# telemetry-4L.net
KiCad netlist of a schematic drawn in EAGLE
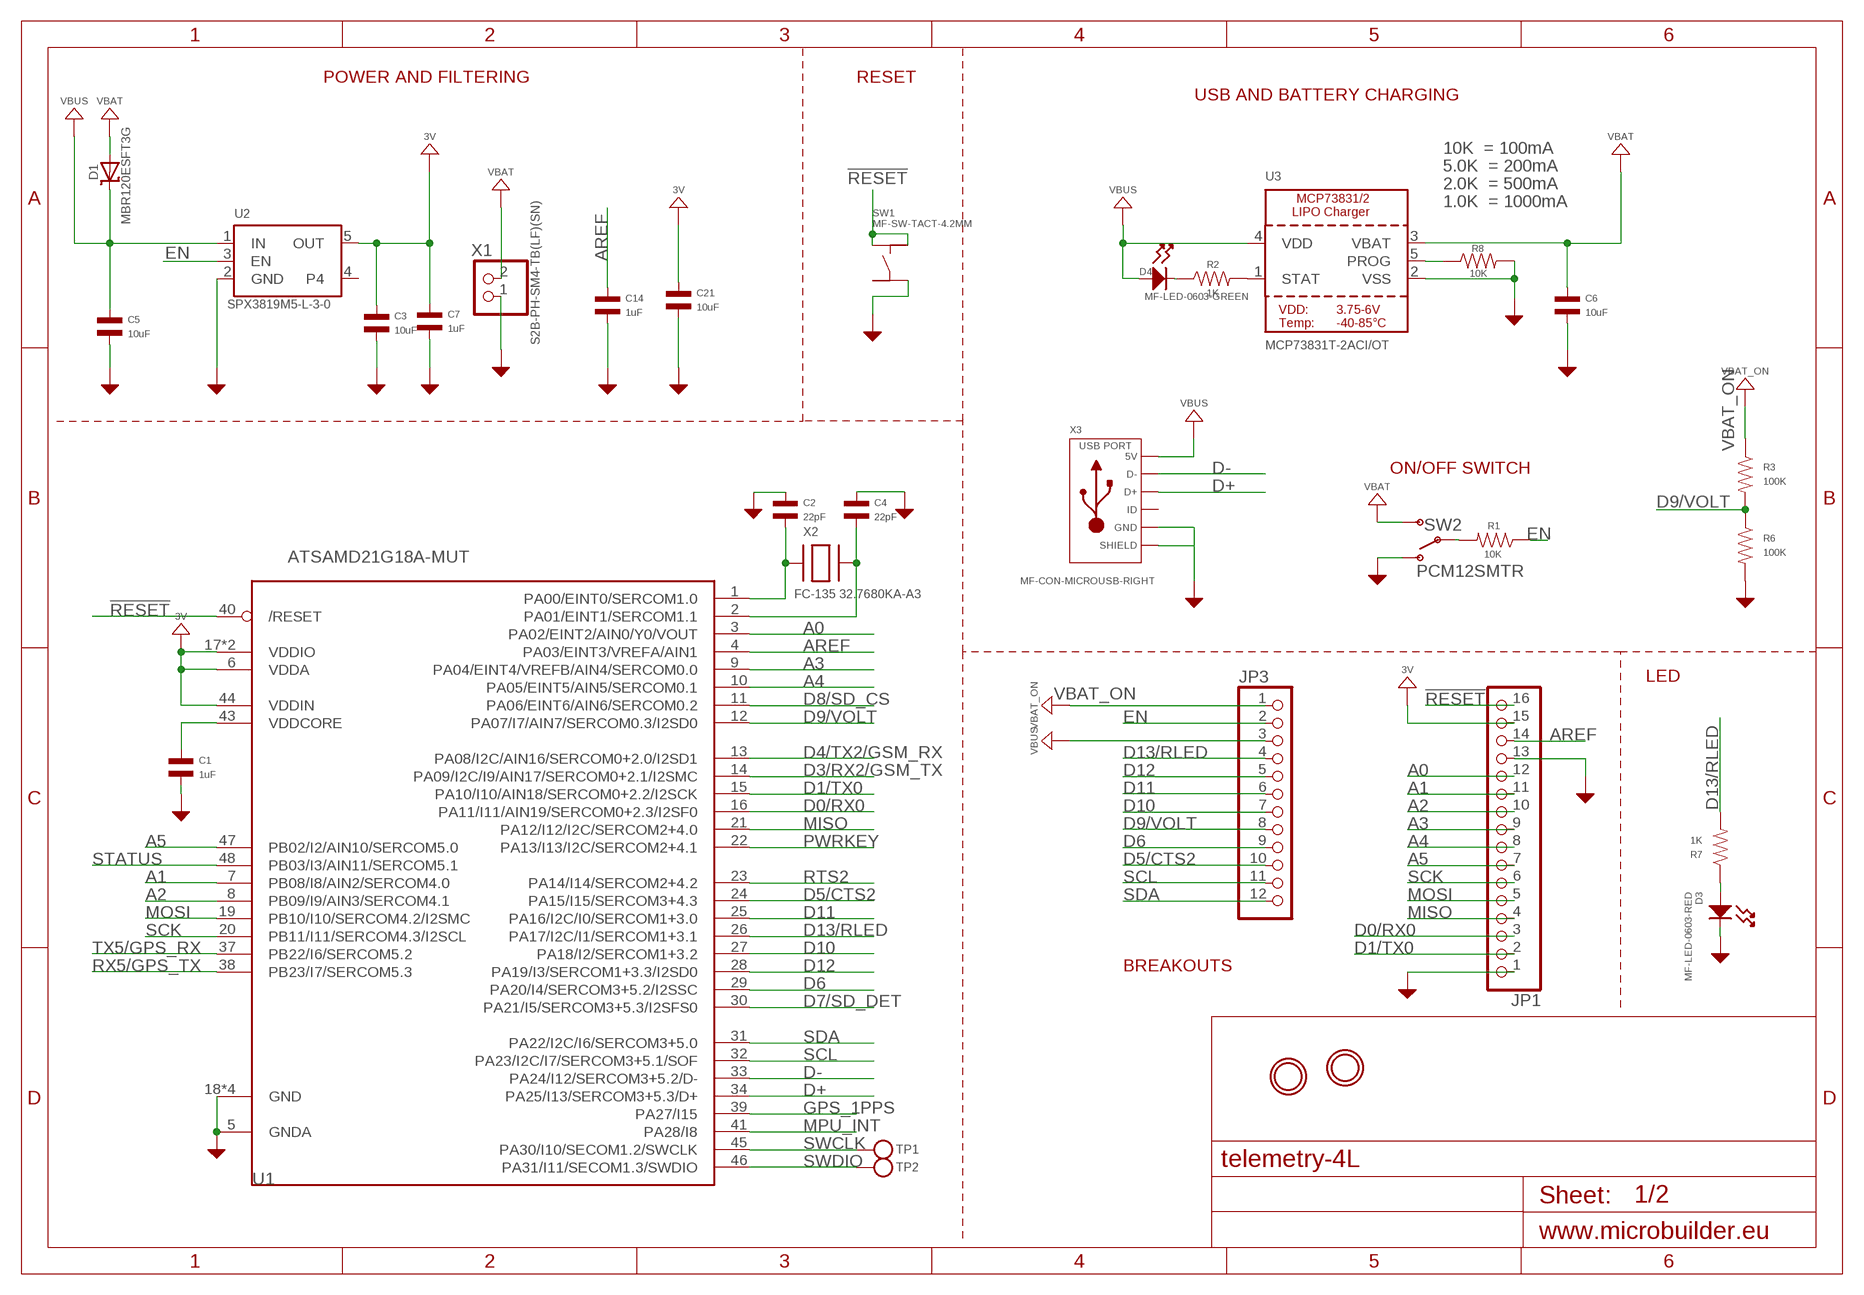
[diagram p0: schematic, sheet 1]
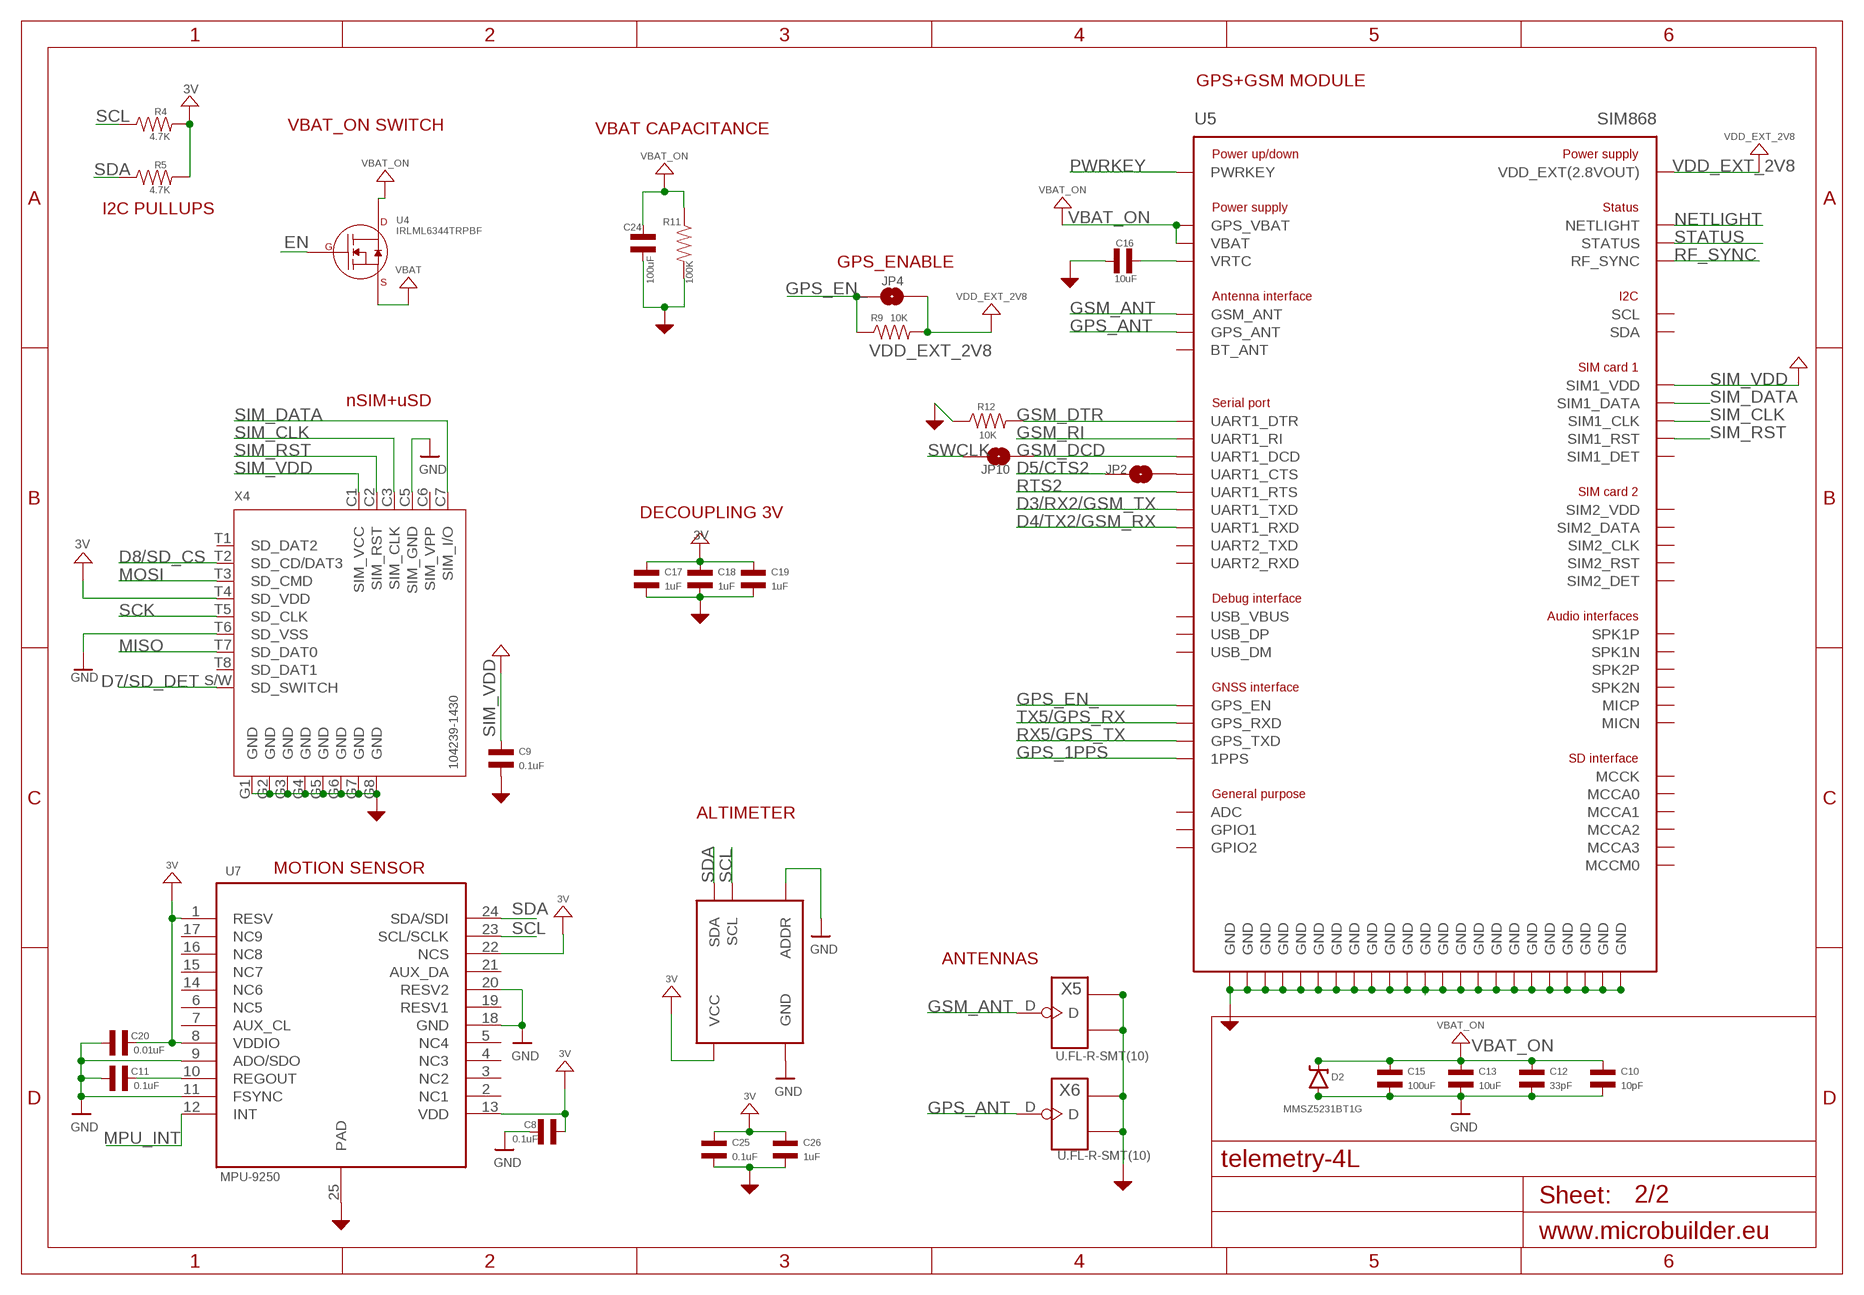
[diagram p1: schematic, sheet 2]

(export (version "E")
  (design (tool "Eeschema 10.0.6"))
  (components
    (comp (ref "C8")
      (value "0.1uF")
      (footprint "eagle-import:C0402")
      (libsource (lib "eagle-import") (part "CAPACITOR_NP_0402"))
    )
    (comp (ref "C9")
      (value "0.1uF")
      (footprint "eagle-import:C0402")
      (libsource (lib "eagle-import") (part "CAPACITOR_NP_0402"))
    )
    (comp (ref "C10")
      (value "10pF")
      (footprint "eagle-import:C0402")
      (fields (field (name "MPN") "GRM1555C1H100JA01J"))
      (libsource (lib "eagle-import") (part "CAPACITOR_NP_0402"))
    )
    (comp (ref "C11")
      (value "0.1uF")
      (footprint "eagle-import:C0402")
      (libsource (lib "eagle-import") (part "CAPACITOR_NP_0402"))
    )
    (comp (ref "C12")
      (value "33pF")
      (footprint "eagle-import:C0402")
      (fields (field (name "MPN") "GRM1555C1H330JA01D"))
      (libsource (lib "eagle-import") (part "CAPACITOR_NP_0402"))
    )
    (comp (ref "C13")
      (value "10uF")
      (footprint "eagle-import:C0603")
      (fields (field (name "MPN") "GRM188R60J106ME47D"))
      (libsource (lib "eagle-import") (part "CAPACITOR_NP_0603"))
    )
    (comp (ref "C15")
      (value "100uF")
      (footprint "eagle-import:C1206")
      (fields (field (name "MPN") "CL31A107MQHNNNE"))
      (libsource (lib "eagle-import") (part "CAPACITOR_NP_1206"))
    )
    (comp (ref "C16")
      (value "10uF")
      (footprint "eagle-import:C0603")
      (fields (field (name "MPN") "GRM188R60J106ME47D"))
      (libsource (lib "eagle-import") (part "CAPACITOR_NP_0603"))
    )
    (comp (ref "C17")
      (value "1uF")
      (footprint "eagle-import:C0402")
      (libsource (lib "eagle-import") (part "CAPACITOR_NP_0402"))
    )
    (comp (ref "C18")
      (value "1uF")
      (footprint "eagle-import:C0402")
      (libsource (lib "eagle-import") (part "CAPACITOR_NP_0402"))
    )
    (comp (ref "C19")
      (value "1uF")
      (footprint "eagle-import:C0402")
      (libsource (lib "eagle-import") (part "CAPACITOR_NP_0402"))
    )
    (comp (ref "C20")
      (value "0.01uF")
      (footprint "eagle-import:C0402")
      (libsource (lib "eagle-import") (part "CAPACITOR_NP_0402"))
    )
    (comp (ref "C24")
      (value "100uF")
      (footprint "eagle-import:C1206")
      (fields (field (name "MPN") "CL31A107MQHNNNE"))
      (libsource (lib "eagle-import") (part "CAPACITOR_NP_1206"))
    )
    (comp (ref "C25")
      (value "0.1uF")
      (footprint "eagle-import:C0402")
      (libsource (lib "eagle-import") (part "CAPACITOR_NP_0402"))
    )
    (comp (ref "C26")
      (value "1uF")
      (footprint "eagle-import:C0402")
      (libsource (lib "eagle-import") (part "CAPACITOR_NP_0402"))
    )
    (comp (ref "D2")
      (value "MMSZ5231BT1G")
      (footprint "eagle-import:SOD-123")
      (fields (field (name "MFR") "ON SEMICONDUCTOR"))
      (libsource (lib "eagle-import") (part "MMSZ5231BT1G"))
    )
    (comp (ref "JP2")
      (value "JUMPER-PAD-2-NOYES_SILK")
      (footprint "eagle-import:PAD-JUMPER-2-NO_YES_SILK")
      (libsource (lib "eagle-import") (part "JUMPER-PAD-2-NOYES_SILK"))
    )
    (comp (ref "JP4")
      (value "JUMPER-PAD-2-NOYES_SILK")
      (footprint "eagle-import:PAD-JUMPER-2-NO_YES_SILK")
      (libsource (lib "eagle-import") (part "JUMPER-PAD-2-NOYES_SILK"))
    )
    (comp (ref "JP10")
      (value "JUMPER-PAD-2-NOYES_SILK")
      (footprint "eagle-import:PAD-JUMPER-2-NO_YES_SILK")
      (libsource (lib "eagle-import") (part "JUMPER-PAD-2-NOYES_SILK"))
    )
    (comp (ref "R4")
      (value "4.7K")
      (footprint "eagle-import:R0402")
      (libsource (lib "eagle-import") (part "RESISTOR_0402"))
    )
    (comp (ref "R5")
      (value "4.7K")
      (footprint "eagle-import:R0402")
      (libsource (lib "eagle-import") (part "RESISTOR_0402"))
    )
    (comp (ref "R9")
      (value "10K")
      (footprint "eagle-import:R0402")
      (libsource (lib "eagle-import") (part "RESISTOR_0402"))
    )
    (comp (ref "R11")
      (value "100K")
      (footprint "eagle-import:R0402")
      (libsource (lib "eagle-import") (part "RESISTOR_0402"))
    )
    (comp (ref "R12")
      (value "10K")
      (footprint "eagle-import:R0402")
      (libsource (lib "eagle-import") (part "RESISTOR_0402"))
    )
    (comp (ref "U4")
      (value "IRLML6344TRPBF")
      (footprint "eagle-import:SOT-23-3")
      (fields (field (name "HOUSEPART") "NO"))
      (libsource (lib "eagle-import") (part "N-CHANNEL_FET_SOT-23-3"))
    )
    (comp (ref "U5")
      (value "SIM868")
      (footprint "eagle-import:SIM868")
      (libsource (lib "eagle-import") (part "SIM868"))
    )
    (comp (ref "U6")
      (value "BMP280")
      (footprint "eagle-import:LGA-8")
      (libsource (lib "eagle-import") (part "BMP280"))
    )
    (comp (ref "U7")
      (value "MPU-9250")
      (footprint "eagle-import:LEAD-QFN24")
      (libsource (lib "eagle-import") (part "MPU-9250"))
    )
    (comp (ref "X4")
      (value "104239-1430")
      (footprint "eagle-import:MOLEX-SD+SIM-104239")
      (fields (field (name "MPN") "VSHO-21-3301") (field (name "MPN_1") "104239-1430"))
      (libsource (lib "eagle-import") (part "MOLEX-SD+SIM-104239"))
    )
    (comp (ref "X5")
      (value "U.FL-R-SMT(10)")
      (footprint "eagle-import:U-FL3P-SMD-2.6X2.6X1.0MM")
      (libsource (lib "eagle-import") (part "ANTENNA-CONN-U-FL(3P)"))
    )
    (comp (ref "X6")
      (value "U.FL-R-SMT(10)")
      (footprint "eagle-import:U-FL3P-SMD-2.6X2.6X1.0MM")
      (libsource (lib "eagle-import") (part "ANTENNA-CONN-U-FL(3P)"))
    )
    (comp (ref "C1")
      (value "1uF")
      (footprint "eagle-import:C0402")
      (libsource (lib "eagle-import") (part "CAPACITOR_NP_0402"))
    )
    (comp (ref "C2")
      (value "22pF")
      (footprint "eagle-import:C0402")
      (libsource (lib "eagle-import") (part "CAPACITOR_NP_0402"))
    )
    (comp (ref "C3")
      (value "10uF")
      (footprint "eagle-import:C0603")
      (fields (field (name "MPN") "GRM188R60J106ME47D"))
      (libsource (lib "eagle-import") (part "CAPACITOR_NP_0603"))
    )
    (comp (ref "C4")
      (value "22pF")
      (footprint "eagle-import:C0402")
      (libsource (lib "eagle-import") (part "CAPACITOR_NP_0402"))
    )
    (comp (ref "C5")
      (value "10uF")
      (footprint "eagle-import:C0603")
      (fields (field (name "MPN") "GRM188R60J106ME47D"))
      (libsource (lib "eagle-import") (part "CAPACITOR_NP_0603"))
    )
    (comp (ref "C6")
      (value "10uF")
      (footprint "eagle-import:C0603")
      (fields (field (name "MPN") "GRM188R60J106ME47D"))
      (libsource (lib "eagle-import") (part "CAPACITOR_NP_0603"))
    )
    (comp (ref "C7")
      (value "1uF")
      (footprint "eagle-import:C0402")
      (libsource (lib "eagle-import") (part "CAPACITOR_NP_0402"))
    )
    (comp (ref "C14")
      (value "1uF")
      (footprint "eagle-import:C0402")
      (libsource (lib "eagle-import") (part "CAPACITOR_NP_0402"))
    )
    (comp (ref "C21")
      (value "10uF")
      (footprint "eagle-import:C0603")
      (fields (field (name "MPN") "GRM188R60J106ME47D"))
      (libsource (lib "eagle-import") (part "CAPACITOR_NP_0603"))
    )
    (comp (ref "D1")
      (value "MBR120ESFT3G")
      (footprint "eagle-import:SOD-123")
      (libsource (lib "eagle-import") (part "DIODE-SCHOTTKYSOD-123"))
    )
    (comp (ref "D3")
      (value "MF-LED-0603-RED")
      (footprint "eagle-import:LED0603")
      (fields (field (name "HOUSEPART") "YES"))
      (libsource (lib "eagle-import") (part "LED_SINGLE-0603-RED"))
    )
    (comp (ref "D4")
      (value "MF-LED-0603-GREEN")
      (footprint "eagle-import:LED0603")
      (fields (field (name "HOUSEPART") "YES"))
      (libsource (lib "eagle-import") (part "LED_SINGLE-0603-GREEN"))
    )
    (comp (ref "JP1")
      (value "HEADER-1X16ROUND")
      (footprint "eagle-import:1X16_ROUND")
      (libsource (lib "eagle-import") (part "HEADER-1X16ROUND"))
    )
    (comp (ref "JP3")
      (value "HEADER-1X12")
      (footprint "eagle-import:1X12_ROUND")
      (libsource (lib "eagle-import") (part "HEADER-1X12"))
    )
    (comp (ref "R1")
      (value "10K")
      (footprint "eagle-import:R0402")
      (libsource (lib "eagle-import") (part "RESISTOR_0402"))
    )
    (comp (ref "R2")
      (value "1K")
      (footprint "eagle-import:R0402")
      (libsource (lib "eagle-import") (part "RESISTOR_0402"))
    )
    (comp (ref "R3")
      (value "100K")
      (footprint "eagle-import:R0402")
      (libsource (lib "eagle-import") (part "RESISTOR_0402"))
    )
    (comp (ref "R6")
      (value "100K")
      (footprint "eagle-import:R0402")
      (libsource (lib "eagle-import") (part "RESISTOR_0402"))
    )
    (comp (ref "R7")
      (value "1K")
      (footprint "eagle-import:R0402")
      (libsource (lib "eagle-import") (part "RESISTOR_0402"))
    )
    (comp (ref "R8")
      (value "10K")
      (footprint "eagle-import:R0402")
      (libsource (lib "eagle-import") (part "RESISTOR_0402"))
    )
    (comp (ref "SW1")
      (value "MF-SW-TACT-4.2MM")
      (footprint "eagle-import:TACT4.2MM")
      (fields (field (name "HOUSEPART") "YES"))
      (libsource (lib "eagle-import") (part "TACT_4.2MM"))
    )
    (comp (ref "SW2")
      (value "PCM12SMTR")
      (footprint "eagle-import:KPS-1290")
      (libsource (lib "eagle-import") (part "SWITCH_SPDT"))
    )
    (comp (ref "TP1")
      (value "TESTPOINTROUND1.5MM")
      (footprint "eagle-import:TESTPOINT_ROUND_1.5MM")
      (libsource (lib "eagle-import") (part "TESTPOINTROUND1.5MM"))
    )
    (comp (ref "TP2")
      (value "TESTPOINTROUND1.5MM")
      (footprint "eagle-import:TESTPOINT_ROUND_1.5MM")
      (libsource (lib "eagle-import") (part "TESTPOINTROUND1.5MM"))
    )
    (comp (ref "U$31")
      (value "MOUNTINGHOLE2.5")
      (footprint "eagle-import:MOUNTINGHOLE_2.5_PLATED")
      (libsource (lib "eagle-import") (part "MOUNTINGHOLE2.5"))
    )
    (comp (ref "U$32")
      (value "MOUNTINGHOLE2.5")
      (footprint "eagle-import:MOUNTINGHOLE_2.5_PLATED")
      (libsource (lib "eagle-import") (part "MOUNTINGHOLE2.5"))
    )
    (comp (ref "U1")
      (value "ATSAMD21G18A-MUT")
      (footprint "eagle-import:TQFN48_7MM")
      (libsource (lib "eagle-import") (part "ATSAMD21J_QFN"))
    )
    (comp (ref "U2")
      (value "SPX3819M5-L-3-0")
      (footprint "eagle-import:SOT23-5")
      (libsource (lib "eagle-import") (part "VREG_SOT23-5"))
    )
    (comp (ref "U3")
      (value "MCP73831T-2ACI/OT")
      (footprint "eagle-import:SOT23-5")
      (libsource (lib "eagle-import") (part "MCP73831/2"))
    )
    (comp (ref "X1")
      (value "S2B-PH-SM4-TB(LF)(SN)")
      (footprint "eagle-import:JSTPH2")
      (libsource (lib "eagle-import") (part "CON_JST_PH_2PIN"))
    )
    (comp (ref "X2")
      (value "FC-135 32.7680KA-A3")
      (footprint "eagle-import:XTAL3215")
      (libsource (lib "eagle-import") (part "XTAL-3.2X1.5"))
    )
    (comp (ref "X3")
      (value "MF-CON-MICROUSB-RIGHT")
      (footprint "eagle-import:MICROUSB-RIGHT")
      (fields (field (name "HOUSEPART") "YES"))
      (libsource (lib "eagle-import") (part "USB_MICRO_RIGHT"))
    )
  )
  (nets
    (net (code "1") (name "+3V") (class "Default")
      (node (ref "C17") (pin "P$1") (pinfunction "P$1_P$1") (pintype "passive"))
      (node (ref "C18") (pin "P$1") (pinfunction "P$1_P$1") (pintype "passive"))
      (node (ref "C19") (pin "P$1") (pinfunction "P$1_P$1") (pintype "passive"))
      (node (ref "C20") (pin "P$2") (pinfunction "P$2_P$2") (pintype "passive"))
      (node (ref "C21") (pin "P$1") (pinfunction "P$1_P$1") (pintype "passive"))
      (node (ref "C25") (pin "P$1") (pinfunction "P$1_P$1") (pintype "passive"))
      (node (ref "C26") (pin "P$1") (pinfunction "P$1_P$1") (pintype "passive"))
      (node (ref "C3") (pin "P$1") (pinfunction "P$1_P$1") (pintype "passive"))
      (node (ref "C7") (pin "P$1") (pinfunction "P$1_P$1") (pintype "passive"))
      (node (ref "C8") (pin "P$2") (pinfunction "P$2_P$2") (pintype "passive"))
      (node (ref "JP1") (pin "15") (pinfunction "15_15") (pintype "passive"))
      (node (ref "R4") (pin "P$2") (pinfunction "P$2_P$2") (pintype "passive"))
      (node (ref "R5") (pin "P$2") (pinfunction "P$2_P$2") (pintype "passive"))
      (node (ref "U1") (pin "17") (pinfunction "VDDIO_17") (pintype "power_in"))
      (node (ref "U1") (pin "36") (pinfunction "VDDIO_36") (pintype "power_in"))
      (node (ref "U1") (pin "44") (pinfunction "VDDIN_44") (pintype "power_in"))
      (node (ref "U1") (pin "6") (pinfunction "VDDA_6") (pintype "power_in"))
      (node (ref "U2") (pin "5") (pinfunction "OUT_5") (pintype "power_in"))
      (node (ref "U6") (pin "P2") (pinfunction "VCC_P2") (pintype "bidirectional"))
      (node (ref "U6") (pin "P6") (pinfunction "VCC_P6") (pintype "bidirectional"))
      (node (ref "U6") (pin "P8") (pinfunction "VCC_P8") (pintype "bidirectional"))
      (node (ref "U7") (pin "1") (pinfunction "RESV_1") (pintype "bidirectional"))
      (node (ref "U7") (pin "13") (pinfunction "VDD_13") (pintype "bidirectional"))
      (node (ref "U7") (pin "22") (pinfunction "NCS_22") (pintype "bidirectional"))
      (node (ref "U7") (pin "8") (pinfunction "VDDIO_8") (pintype "bidirectional"))
      (node (ref "X4") (pin "T4") (pinfunction "SD_VDD_T4") (pintype "bidirectional"))
    )
    (net (code "2") (name "A0") (class "Default")
      (node (ref "JP1") (pin "12") (pinfunction "12_12") (pintype "passive"))
      (node (ref "U1") (pin "3") (pinfunction "PA02/EINT2/AIN0/Y0/VOUT_3") (pintype "bidirectional"))
    )
    (net (code "3") (name "A1") (class "Default")
      (node (ref "JP1") (pin "11") (pinfunction "11_11") (pintype "passive"))
      (node (ref "U1") (pin "7") (pinfunction "PB08/I8/AIN2/SERCOM4.0_7") (pintype "bidirectional"))
    )
    (net (code "4") (name "A2") (class "Default")
      (node (ref "JP1") (pin "10") (pinfunction "10_10") (pintype "passive"))
      (node (ref "U1") (pin "8") (pinfunction "PB09/I9/AIN3/SERCOM4.1_8") (pintype "bidirectional"))
    )
    (net (code "5") (name "A3") (class "Default")
      (node (ref "JP1") (pin "9") (pinfunction "9_9") (pintype "passive"))
      (node (ref "U1") (pin "9") (pinfunction "PA04/EINT4/VREFB/AIN4/SERCOM0.0_9") (pintype "bidirectional"))
    )
    (net (code "6") (name "A4") (class "Default")
      (node (ref "JP1") (pin "8") (pinfunction "8_8") (pintype "passive"))
      (node (ref "U1") (pin "10") (pinfunction "PA05/EINT5/AIN5/SERCOM0.1_10") (pintype "bidirectional"))
    )
    (net (code "7") (name "A5") (class "Default")
      (node (ref "JP1") (pin "7") (pinfunction "7_7") (pintype "passive"))
      (node (ref "U1") (pin "47") (pinfunction "PB02/I2/AIN10/SERCOM5.0_47") (pintype "bidirectional"))
    )
    (net (code "8") (name "AREF") (class "Default")
      (node (ref "C14") (pin "P$1") (pinfunction "P$1_P$1") (pintype "passive"))
      (node (ref "JP1") (pin "14") (pinfunction "14_14") (pintype "passive"))
      (node (ref "U1") (pin "4") (pinfunction "PA03/EINT3/VREFA/AIN1_4") (pintype "bidirectional"))
    )
    (net (code "9") (name "D+") (class "Default")
      (node (ref "U1") (pin "34") (pinfunction "PA25/I13/SERCOM3+5.3/D+_34") (pintype "bidirectional"))
      (node (ref "X3") (pin "3") (pinfunction "D+_3") (pintype "bidirectional"))
    )
    (net (code "10") (name "D-") (class "Default")
      (node (ref "U1") (pin "33") (pinfunction "PA24/I12/SERCOM3+5.2/D-_33") (pintype "bidirectional"))
      (node (ref "X3") (pin "2") (pinfunction "D-_2") (pintype "bidirectional"))
    )
    (net (code "11") (name "D0{slash}RX0") (class "Default")
      (node (ref "JP1") (pin "3") (pinfunction "3_3") (pintype "passive"))
      (node (ref "U1") (pin "16") (pinfunction "PA11/I11/AIN19/SERCOM0+2.3/I2SF0_16") (pintype "bidirectional"))
    )
    (net (code "12") (name "D1{slash}TX0") (class "Default")
      (node (ref "JP1") (pin "2") (pinfunction "2_2") (pintype "passive"))
      (node (ref "U1") (pin "15") (pinfunction "PA10/I10/AIN18/SERCOM0+2.2/I2SCK_15") (pintype "bidirectional"))
    )
    (net (code "13") (name "D3{slash}RX2{slash}GSM_TX") (class "Default")
      (node (ref "U1") (pin "14") (pinfunction "PA09/I2C/I9/AIN17/SERCOM0+2.1/I2SMC_14") (pintype "bidirectional"))
      (node (ref "U5") (pin "1_") (pinfunction "UART1_TXD_1_") (pintype "output"))
    )
    (net (code "14") (name "D4{slash}TX2{slash}GSM_RX") (class "Default")
      (node (ref "U1") (pin "13") (pinfunction "PA08/I2C/AIN16/SERCOM0+2.0/I2SD1_13") (pintype "bidirectional"))
      (node (ref "U5") (pin "2_") (pinfunction "UART1_RXD_2_") (pintype "input"))
    )
    (net (code "15") (name "D5{slash}CTS2") (class "Default")
      (node (ref "JP2") (pin "1") (pinfunction "1_1") (pintype "passive"))
      (node (ref "JP3") (pin "10") (pinfunction "10_10") (pintype "passive"))
      (node (ref "U1") (pin "24") (pinfunction "PA15/I15/SERCOM3+4.3_24") (pintype "bidirectional"))
    )
    (net (code "16") (name "D6") (class "Default")
      (node (ref "JP3") (pin "9") (pinfunction "9_9") (pintype "passive"))
      (node (ref "U1") (pin "29") (pinfunction "PA20/I4/SERCOM3+5.2/I2SSC_29") (pintype "bidirectional"))
    )
    (net (code "17") (name "D7{slash}SD_DET") (class "Default")
      (node (ref "U1") (pin "30") (pinfunction "PA21/I5/SERCOM3+5.3/I2SFS0_30") (pintype "bidirectional"))
      (node (ref "X4") (pin "S/W") (pinfunction "SD_SWITCH_S/W") (pintype "bidirectional"))
    )
    (net (code "18") (name "D8{slash}SD_CS") (class "Default")
      (node (ref "U1") (pin "11") (pinfunction "PA06/EINT6/AIN6/SERCOM0.2_11") (pintype "bidirectional"))
      (node (ref "X4") (pin "T2") (pinfunction "SD_CD/DAT3_T2") (pintype "bidirectional"))
    )
    (net (code "19") (name "D9{slash}VOLT") (class "Default")
      (node (ref "JP3") (pin "8") (pinfunction "8_8") (pintype "passive"))
      (node (ref "R3") (pin "P$2") (pinfunction "P$2_P$2") (pintype "passive"))
      (node (ref "R6") (pin "P$1") (pinfunction "P$1_P$1") (pintype "passive"))
      (node (ref "U1") (pin "12") (pinfunction "PA07/I7/AIN7/SERCOM0.3/I2SD0_12") (pintype "bidirectional"))
    )
    (net (code "20") (name "D10") (class "Default")
      (node (ref "JP3") (pin "7") (pinfunction "7_7") (pintype "passive"))
      (node (ref "U1") (pin "27") (pinfunction "PA18/I2/SERCOM1+3.2_27") (pintype "bidirectional"))
    )
    (net (code "21") (name "D11") (class "Default")
      (node (ref "JP3") (pin "6") (pinfunction "6_6") (pintype "passive"))
      (node (ref "U1") (pin "25") (pinfunction "PA16/I2C/I0/SERCOM1+3.0_25") (pintype "bidirectional"))
    )
    (net (code "22") (name "D12") (class "Default")
      (node (ref "JP3") (pin "5") (pinfunction "5_5") (pintype "passive"))
      (node (ref "U1") (pin "28") (pinfunction "PA19/I3/SERCOM1+3.3/I2SD0_28") (pintype "bidirectional"))
    )
    (net (code "23") (name "D13{slash}RLED") (class "Default")
      (node (ref "JP3") (pin "4") (pinfunction "4_4") (pintype "passive"))
      (node (ref "R7") (pin "P$2") (pinfunction "P$2_P$2") (pintype "passive"))
      (node (ref "U1") (pin "26") (pinfunction "PA17/I2C/I1/SERCOM1+3.1_26") (pintype "bidirectional"))
    )
    (net (code "24") (name "EN") (class "Default")
      (node (ref "JP3") (pin "2") (pinfunction "2_2") (pintype "passive"))
      (node (ref "R1") (pin "P$1") (pinfunction "P$1_P$1") (pintype "passive"))
      (node (ref "U2") (pin "3") (pinfunction "EN_3") (pintype "input"))
      (node (ref "U4") (pin "P$1") (pinfunction "GATE_P$1") (pintype "bidirectional"))
    )
    (net (code "25") (name "GND") (class "Default")
      (node (ref "C1") (pin "P$2") (pinfunction "P$2_P$2") (pintype "passive"))
      (node (ref "C10") (pin "P$2") (pinfunction "P$2_P$2") (pintype "passive"))
      (node (ref "C11") (pin "P$1") (pinfunction "P$1_P$1") (pintype "passive"))
      (node (ref "C12") (pin "P$2") (pinfunction "P$2_P$2") (pintype "passive"))
      (node (ref "C13") (pin "P$2") (pinfunction "P$2_P$2") (pintype "passive"))
      (node (ref "C14") (pin "P$2") (pinfunction "P$2_P$2") (pintype "passive"))
      (node (ref "C15") (pin "P$2") (pinfunction "P$2_P$2") (pintype "passive"))
      (node (ref "C16") (pin "P$1") (pinfunction "P$1_P$1") (pintype "passive"))
      (node (ref "C17") (pin "P$2") (pinfunction "P$2_P$2") (pintype "passive"))
      (node (ref "C18") (pin "P$2") (pinfunction "P$2_P$2") (pintype "passive"))
      (node (ref "C19") (pin "P$2") (pinfunction "P$2_P$2") (pintype "passive"))
      (node (ref "C2") (pin "P$1") (pinfunction "P$1_P$1") (pintype "passive"))
      (node (ref "C20") (pin "P$1") (pinfunction "P$1_P$1") (pintype "passive"))
      (node (ref "C21") (pin "P$2") (pinfunction "P$2_P$2") (pintype "passive"))
      (node (ref "C24") (pin "P$2") (pinfunction "P$2_P$2") (pintype "passive"))
      (node (ref "C25") (pin "P$2") (pinfunction "P$2_P$2") (pintype "passive"))
      (node (ref "C26") (pin "P$2") (pinfunction "P$2_P$2") (pintype "passive"))
      (node (ref "C3") (pin "P$2") (pinfunction "P$2_P$2") (pintype "passive"))
      (node (ref "C4") (pin "P$1") (pinfunction "P$1_P$1") (pintype "passive"))
      (node (ref "C5") (pin "P$2") (pinfunction "P$2_P$2") (pintype "passive"))
      (node (ref "C6") (pin "P$2") (pinfunction "P$2_P$2") (pintype "passive"))
      (node (ref "C7") (pin "P$2") (pinfunction "P$2_P$2") (pintype "passive"))
      (node (ref "C8") (pin "P$1") (pinfunction "P$1_P$1") (pintype "passive"))
      (node (ref "C9") (pin "P$2") (pinfunction "P$2_P$2") (pintype "passive"))
      (node (ref "D2") (pin "A") (pinfunction "A_A") (pintype "passive"))
      (node (ref "D3") (pin "CATHODE") (pinfunction "CATHODE_CATHODE") (pintype "power_in"))
      (node (ref "JP1") (pin "1") (pinfunction "1_1") (pintype "passive"))
      (node (ref "JP1") (pin "13") (pinfunction "13_13") (pintype "passive"))
      (node (ref "R11") (pin "P$2") (pinfunction "P$2_P$2") (pintype "passive"))
      (node (ref "R12") (pin "P$1") (pinfunction "P$1_P$1") (pintype "passive"))
      (node (ref "R6") (pin "P$2") (pinfunction "P$2_P$2") (pintype "passive"))
      (node (ref "R8") (pin "P$2") (pinfunction "P$2_P$2") (pintype "passive"))
      (node (ref "SW1") (pin "P$4") (pinfunction "P$4_P$4") (pintype "bidirectional"))
      (node (ref "SW2") (pin "O") (pinfunction "O_O") (pintype "passive"))
      (node (ref "U1") (pin "18") (pinfunction "GND_18") (pintype "power_in"))
      (node (ref "U1") (pin "35") (pinfunction "GND_35") (pintype "power_in"))
      (node (ref "U1") (pin "42") (pinfunction "GND_42") (pintype "power_in"))
      (node (ref "U1") (pin "5") (pinfunction "GNDA_5") (pintype "power_in"))
      (node (ref "U1") (pin "THERMAL") (pinfunction "GND_THERMAL") (pintype "power_in"))
      (node (ref "U2") (pin "2") (pinfunction "GND_2") (pintype "power_in"))
      (node (ref "U3") (pin "2") (pinfunction "VSS_2") (pintype "power_in"))
      (node (ref "U5") (pin "13_") (pinfunction "GND_13_") (pintype "power_in"))
      (node (ref "U5") (pin "19_") (pinfunction "GND_19_") (pintype "power_in"))
      (node (ref "U5") (pin "21_") (pinfunction "GND_21_") (pintype "power_in"))
      (node (ref "U5") (pin "27_") (pinfunction "GND_27_") (pintype "power_in"))
      (node (ref "U5") (pin "30_") (pinfunction "GND_30_") (pintype "power_in"))
      (node (ref "U5") (pin "31_") (pinfunction "GND_31_") (pintype "power_in"))
      (node (ref "U5") (pin "33_") (pinfunction "GND_33_") (pintype "power_in"))
      (node (ref "U5") (pin "36_") (pinfunction "GND_36_") (pintype "power_in"))
      (node (ref "U5") (pin "37_") (pinfunction "GND_37_") (pintype "power_in"))
      (node (ref "U5") (pin "45_") (pinfunction "GND_45_") (pintype "power_in"))
      (node (ref "U5") (pin "63_") (pinfunction "GND_63_") (pintype "power_in"))
      (node (ref "U5") (pin "66_") (pinfunction "GND_66_") (pintype "power_in"))
      (node (ref "U5") (pin "67_") (pinfunction "GND_67_") (pintype "power_in"))
      (node (ref "U5") (pin "69_") (pinfunction "GND_69_") (pintype "power_in"))
      (node (ref "U5") (pin "70_") (pinfunction "GND_70_") (pintype "power_in"))
      (node (ref "U5") (pin "71_") (pinfunction "GND_71_") (pintype "power_in"))
      (node (ref "U5") (pin "72_") (pinfunction "GND_72_") (pintype "power_in"))
      (node (ref "U5") (pin "73_") (pinfunction "GND_73_") (pintype "power_in"))
      (node (ref "U5") (pin "74_") (pinfunction "GND_74_") (pintype "power_in"))
      (node (ref "U5") (pin "75_") (pinfunction "GND_75_") (pintype "power_in"))
      (node (ref "U5") (pin "76_") (pinfunction "GND_76_") (pintype "power_in"))
      (node (ref "U5") (pin "77_") (pinfunction "GND_77_") (pintype "power_in"))
      (node (ref "U5") (pin "8_") (pinfunction "GND_8_") (pintype "power_in"))
      (node (ref "U6") (pin "P1") (pinfunction "GND_P1") (pintype "bidirectional"))
      (node (ref "U6") (pin "P5") (pinfunction "ADDR_P5") (pintype "bidirectional"))
      (node (ref "U6") (pin "P7") (pinfunction "GND_P7") (pintype "bidirectional"))
      (node (ref "U7") (pin "11") (pinfunction "FSYNC_11") (pintype "bidirectional"))
      (node (ref "U7") (pin "18") (pinfunction "GND_18") (pintype "bidirectional"))
      (node (ref "U7") (pin "20") (pinfunction "RESV2_20") (pintype "bidirectional"))
      (node (ref "U7") (pin "25") (pinfunction "PAD_25") (pintype "bidirectional"))
      (node (ref "U7") (pin "9") (pinfunction "ADO/SDO_9") (pintype "bidirectional"))
      (node (ref "X1") (pin "1") (pinfunction "1_1") (pintype "passive"))
      (node (ref "X3") (pin "5") (pinfunction "GND_5") (pintype "power_in"))
      (node (ref "X3") (pin "S1") (pinfunction "SLD_S1") (pintype "power_in"))
      (node (ref "X3") (pin "S2") (pinfunction "SLD_S2") (pintype "power_in"))
      (node (ref "X3") (pin "S3") (pinfunction "SLD_S3") (pintype "power_in"))
      (node (ref "X3") (pin "S4") (pinfunction "SLD_S4") (pintype "power_in"))
      (node (ref "X3") (pin "S5") (pinfunction "SLD_S5") (pintype "power_in"))
      (node (ref "X3") (pin "S6") (pinfunction "SLD_S6") (pintype "power_in"))
      (node (ref "X4") (pin "C5") (pinfunction "SIM_GND_C5") (pintype "bidirectional"))
      (node (ref "X4") (pin "G1") (pinfunction "GND_G1") (pintype "power_in"))
      (node (ref "X4") (pin "G2") (pinfunction "GND_G2") (pintype "power_in"))
      (node (ref "X4") (pin "G3") (pinfunction "GND_G3") (pintype "power_in"))
      (node (ref "X4") (pin "G4") (pinfunction "GND_G4") (pintype "power_in"))
      (node (ref "X4") (pin "G5") (pinfunction "GND_G5") (pintype "power_in"))
      (node (ref "X4") (pin "G6") (pinfunction "GND_G6") (pintype "power_in"))
      (node (ref "X4") (pin "G7") (pinfunction "GND_G7") (pintype "power_in"))
      (node (ref "X4") (pin "G8") (pinfunction "GND_G8") (pintype "power_in"))
      (node (ref "X4") (pin "T6") (pinfunction "SD_VSS_T6") (pintype "bidirectional"))
      (node (ref "X5") (pin "GND1") (pinfunction "GND1_GND1") (pintype "bidirectional"))
      (node (ref "X5") (pin "GND2") (pinfunction "GND2_GND2") (pintype "bidirectional"))
      (node (ref "X6") (pin "GND1") (pinfunction "GND1_GND1") (pintype "bidirectional"))
      (node (ref "X6") (pin "GND2") (pinfunction "GND2_GND2") (pintype "bidirectional"))
    )
    (net (code "26") (name "GPS_1PPS") (class "Default")
      (node (ref "U1") (pin "39") (pinfunction "PA27/I15_39") (pintype "bidirectional"))
      (node (ref "U5") (pin "60_") (pinfunction "1PPS_60_") (pintype "input"))
    )
    (net (code "27") (name "GPS_ANT") (class "Default")
      (node (ref "U5") (pin "68_") (pinfunction "GPS_ANT_68_") (pintype "bidirectional"))
      (node (ref "X6") (pin "D") (pinfunction "D_D") (pintype "bidirectional"))
    )
    (net (code "28") (name "GPS_EN_") (class "Default")
      (node (ref "JP4") (pin "1") (pinfunction "1_1") (pintype "passive"))
      (node (ref "R9") (pin "P$1") (pinfunction "P$1_P$1") (pintype "passive"))
      (node (ref "U5") (pin "59_") (pinfunction "GPS_EN_59_") (pintype "input"))
    )
    (net (code "29") (name "GSM_ANT") (class "Default")
      (node (ref "U5") (pin "32_") (pinfunction "GSM_ANT_32_") (pintype "input"))
      (node (ref "X5") (pin "D") (pinfunction "D_D") (pintype "bidirectional"))
    )
    (net (code "30") (name "GSM_DCD") (class "Default")
      (node (ref "JP10") (pin "2") (pinfunction "2_2") (pintype "passive"))
      (node (ref "U5") (pin "5_") (pinfunction "UART1_DCD_5_") (pintype "output"))
    )
    (net (code "31") (name "GSM_DTR") (class "Default")
      (node (ref "R12") (pin "P$2") (pinfunction "P$2_P$2") (pintype "passive"))
      (node (ref "U5") (pin "6_") (pinfunction "UART1_DTR_6_") (pintype "input"))
    )
    (net (code "32") (name "GSM_RI") (class "Default")
      (node (ref "U5") (pin "7_") (pinfunction "UART1_RI_7_") (pintype "output"))
    )
    (net (code "33") (name "MISO") (class "Default")
      (node (ref "JP1") (pin "4") (pinfunction "4_4") (pintype "passive"))
      (node (ref "U1") (pin "21") (pinfunction "PA12/I12/I2C/SERCOM2+4.0_21") (pintype "bidirectional"))
      (node (ref "X4") (pin "T7") (pinfunction "SD_DAT0_T7") (pintype "bidirectional"))
    )
    (net (code "34") (name "MOSI") (class "Default")
      (node (ref "JP1") (pin "5") (pinfunction "5_5") (pintype "passive"))
      (node (ref "U1") (pin "19") (pinfunction "PB10/I10/SERCOM4.2/I2SMC_19") (pintype "bidirectional"))
      (node (ref "X4") (pin "T3") (pinfunction "SD_CMD_T3") (pintype "bidirectional"))
    )
    (net (code "35") (name "MPU_INT") (class "Default")
      (node (ref "U1") (pin "41") (pinfunction "PA28/I8_41") (pintype "bidirectional"))
      (node (ref "U7") (pin "12") (pinfunction "INT_12") (pintype "bidirectional"))
    )
    (net (code "36") (name "NETLIGHT") (class "Default")
      (node (ref "U5") (pin "41_") (pinfunction "NETLIGHT_41_") (pintype "output"))
    )
    (net (code "37") (name "Net-(D3-PadANODE)") (class "Default")
      (node (ref "D3") (pin "ANODE") (pinfunction "ANODE_ANODE") (pintype "power_in"))
      (node (ref "R7") (pin "P$1") (pinfunction "P$1_P$1") (pintype "passive"))
    )
    (net (code "38") (name "Net-(D4-PadCATHODE)") (class "Default")
      (node (ref "D4") (pin "CATHODE") (pinfunction "CATHODE_CATHODE") (pintype "power_in"))
      (node (ref "R2") (pin "P$1") (pinfunction "P$1_P$1") (pintype "passive"))
    )
    (net (code "39") (name "Net-(R1-PadP$2)") (class "Default")
      (node (ref "R1") (pin "P$2") (pinfunction "P$2_P$2") (pintype "passive"))
      (node (ref "SW2") (pin "P") (pinfunction "P_P") (pintype "passive"))
    )
    (net (code "40") (name "Net-(U1-PA00{slash}EINT0{slash}SERCOM1.0)") (class "Default")
      (node (ref "C2") (pin "P$2") (pinfunction "P$2_P$2") (pintype "passive"))
      (node (ref "U1") (pin "1") (pinfunction "PA00/EINT0/SERCOM1.0_1") (pintype "bidirectional"))
      (node (ref "X2") (pin "P$1") (pinfunction "P$1_P$1") (pintype "bidirectional"))
    )
    (net (code "41") (name "Net-(U1-PA01{slash}EINT1{slash}SERCOM1.1)") (class "Default")
      (node (ref "C4") (pin "P$2") (pinfunction "P$2_P$2") (pintype "passive"))
      (node (ref "U1") (pin "2") (pinfunction "PA01/EINT1/SERCOM1.1_2") (pintype "bidirectional"))
      (node (ref "X2") (pin "P$2") (pinfunction "P$2_P$2") (pintype "bidirectional"))
    )
    (net (code "42") (name "Net-(U1-VDDCORE)") (class "Default")
      (node (ref "C1") (pin "P$1") (pinfunction "P$1_P$1") (pintype "passive"))
      (node (ref "U1") (pin "43") (pinfunction "VDDCORE_43") (pintype "power_in"))
    )
    (net (code "43") (name "Net-(U3-PROG)") (class "Default")
      (node (ref "R8") (pin "P$1") (pinfunction "P$1_P$1") (pintype "passive"))
      (node (ref "U3") (pin "5") (pinfunction "PROG_5") (pintype "input"))
    )
    (net (code "44") (name "Net-(U3-STAT)") (class "Default")
      (node (ref "R2") (pin "P$2") (pinfunction "P$2_P$2") (pintype "passive"))
      (node (ref "U3") (pin "1") (pinfunction "STAT_1") (pintype "output"))
    )
    (net (code "45") (name "Net-(U5-UART1_CTS)") (class "Default")
      (node (ref "JP2") (pin "2") (pinfunction "2_2") (pintype "passive"))
      (node (ref "U5") (pin "4_") (pinfunction "UART1_CTS_4_") (pintype "output"))
    )
    (net (code "46") (name "Net-(U5-VRTC)") (class "Default")
      (node (ref "C16") (pin "P$2") (pinfunction "P$2_P$2") (pintype "passive"))
      (node (ref "U5") (pin "28_") (pinfunction "VRTC_28_") (pintype "power_in"))
    )
    (net (code "47") (name "Net-(U7-REGOUT)") (class "Default")
      (node (ref "C11") (pin "P$2") (pinfunction "P$2_P$2") (pintype "passive"))
      (node (ref "U7") (pin "10") (pinfunction "REGOUT_10") (pintype "bidirectional"))
    )
    (net (code "48") (name "PWRKEY") (class "Default")
      (node (ref "U1") (pin "22") (pinfunction "PA13/I13/I2C/SERCOM2+4.1_22") (pintype "bidirectional"))
      (node (ref "U5") (pin "39_") (pinfunction "PWRKEY_39_") (pintype "input"))
    )
    (net (code "49") (name "RF_SYNC") (class "Default")
      (node (ref "U5") (pin "29_") (pinfunction "RF_SYNC_29_") (pintype "output"))
    )
    (net (code "50") (name "RTS2") (class "Default")
      (node (ref "U1") (pin "23") (pinfunction "PA14/I14/SERCOM2+4.2_23") (pintype "bidirectional"))
      (node (ref "U5") (pin "3_") (pinfunction "UART1_RTS_3_") (pintype "input"))
    )
    (net (code "51") (name "RX5{slash}GPS_TX") (class "Default")
      (node (ref "U1") (pin "38") (pinfunction "PB23/I7/SERCOM5.3_38") (pintype "bidirectional"))
      (node (ref "U5") (pin "61_") (pinfunction "GPS_TXD_61_") (pintype "output"))
    )
    (net (code "52") (name "SCK") (class "Default")
      (node (ref "JP1") (pin "6") (pinfunction "6_6") (pintype "passive"))
      (node (ref "U1") (pin "20") (pinfunction "PB11/I11/SERCOM4.3/I2SCL_20") (pintype "bidirectional"))
      (node (ref "X4") (pin "T5") (pinfunction "SD_CLK_T5") (pintype "bidirectional"))
    )
    (net (code "53") (name "SCL") (class "Default")
      (node (ref "JP3") (pin "11") (pinfunction "11_11") (pintype "passive"))
      (node (ref "R4") (pin "P$1") (pinfunction "P$1_P$1") (pintype "passive"))
      (node (ref "U1") (pin "32") (pinfunction "PA23/I2C/I7/SERCOM3+5.1/SOF_32") (pintype "bidirectional"))
      (node (ref "U6") (pin "P4") (pinfunction "SCL_P4") (pintype "bidirectional"))
      (node (ref "U7") (pin "23") (pinfunction "SCL/SCLK_23") (pintype "bidirectional"))
    )
    (net (code "54") (name "SDA") (class "Default")
      (node (ref "JP3") (pin "12") (pinfunction "12_12") (pintype "passive"))
      (node (ref "R5") (pin "P$1") (pinfunction "P$1_P$1") (pintype "passive"))
      (node (ref "U1") (pin "31") (pinfunction "PA22/I2C/I6/SERCOM3+5.0_31") (pintype "bidirectional"))
      (node (ref "U6") (pin "P3") (pinfunction "SDA_P3") (pintype "bidirectional"))
      (node (ref "U7") (pin "24") (pinfunction "SDA/SDI_24") (pintype "bidirectional"))
    )
    (net (code "55") (name "SIM2_VDD") (class "Default")
      (node (ref "U5") (pin "56_") (pinfunction "SIM2_VDD_56_") (pintype "power_in"))
    )
    (net (code "56") (name "SIM_CLK") (class "Default")
      (node (ref "U5") (pin "16_") (pinfunction "SIM1_CLK_16_") (pintype "output"))
      (node (ref "X4") (pin "C3") (pinfunction "SIM_CLK_C3") (pintype "bidirectional"))
    )
    (net (code "57") (name "SIM_DATA") (class "Default")
      (node (ref "U5") (pin "15_") (pinfunction "SIM1_DATA_15_") (pintype "bidirectional"))
      (node (ref "X4") (pin "C7") (pinfunction "SIM_I/O_C7") (pintype "bidirectional"))
    )
    (net (code "58") (name "SIM_RST") (class "Default")
      (node (ref "U5") (pin "17_") (pinfunction "SIM1_RST_17_") (pintype "output"))
      (node (ref "X4") (pin "C2") (pinfunction "SIM_RST_C2") (pintype "bidirectional"))
    )
    (net (code "59") (name "SIM_VDD") (class "Default")
      (node (ref "C9") (pin "P$1") (pinfunction "P$1_P$1") (pintype "passive"))
      (node (ref "U5") (pin "18_") (pinfunction "SIM1_VDD_18_") (pintype "power_in"))
      (node (ref "X4") (pin "C1") (pinfunction "SIM_VCC_C1") (pintype "bidirectional"))
    )
    (net (code "60") (name "STATUS") (class "Default")
      (node (ref "U1") (pin "48") (pinfunction "PB03/I3/AIN11/SERCOM5.1_48") (pintype "bidirectional"))
      (node (ref "U5") (pin "42_") (pinfunction "STATUS_42_") (pintype "output"))
    )
    (net (code "61") (name "SWCLK") (class "Default")
      (node (ref "JP10") (pin "1") (pinfunction "1_1") (pintype "passive"))
      (node (ref "TP1") (pin "P$1") (pinfunction "P$1_P$1") (pintype "bidirectional"))
      (node (ref "U1") (pin "45") (pinfunction "PA30/I10/SECOM1.2/SWCLK_45") (pintype "bidirectional"))
    )
    (net (code "62") (name "SWDIO") (class "Default")
      (node (ref "TP2") (pin "P$1") (pinfunction "P$1_P$1") (pintype "bidirectional"))
      (node (ref "U1") (pin "46") (pinfunction "PA31/I11/SECOM1.3/SWDIO_46") (pintype "bidirectional"))
    )
    (net (code "63") (name "TX5{slash}GPS_RX") (class "Default")
      (node (ref "U1") (pin "37") (pinfunction "PB22/I6/SERCOM5.2_37") (pintype "bidirectional"))
      (node (ref "U5") (pin "62_") (pinfunction "GPS_RXD_62_") (pintype "input"))
    )
    (net (code "64") (name "USB_VBUS") (class "Default")
      (node (ref "U5") (pin "24_") (pinfunction "USB_VBUS_24_") (pintype "power_in"))
    )
    (net (code "65") (name "VBAT") (class "Default")
      (node (ref "C6") (pin "P$1") (pinfunction "P$1_P$1") (pintype "passive"))
      (node (ref "D1") (pin "A") (pinfunction "A_A") (pintype "passive"))
      (node (ref "SW2") (pin "S") (pinfunction "S_S") (pintype "passive"))
      (node (ref "U3") (pin "3") (pinfunction "VBAT_3") (pintype "power_in"))
      (node (ref "U4") (pin "P$2") (pinfunction "SOURCE_P$2") (pintype "bidirectional"))
      (node (ref "X1") (pin "2") (pinfunction "2_2") (pintype "passive"))
    )
    (net (code "66") (name "VBAT_ON") (class "Default")
      (node (ref "C10") (pin "P$1") (pinfunction "P$1_P$1") (pintype "passive"))
      (node (ref "C12") (pin "P$1") (pinfunction "P$1_P$1") (pintype "passive"))
      (node (ref "C13") (pin "P$1") (pinfunction "P$1_P$1") (pintype "passive"))
      (node (ref "C15") (pin "P$1") (pinfunction "P$1_P$1") (pintype "passive"))
      (node (ref "C24") (pin "P$1") (pinfunction "P$1_P$1") (pintype "passive"))
      (node (ref "D2") (pin "C") (pinfunction "C_C") (pintype "passive"))
      (node (ref "JP3") (pin "1") (pinfunction "1_1") (pintype "passive"))
      (node (ref "R11") (pin "P$1") (pinfunction "P$1_P$1") (pintype "passive"))
      (node (ref "R3") (pin "P$1") (pinfunction "P$1_P$1") (pintype "passive"))
      (node (ref "U4") (pin "P$3") (pinfunction "DRAIN_P$3") (pintype "bidirectional"))
      (node (ref "U5") (pin "34_") (pinfunction "GPS_VBAT_34_") (pintype "power_in"))
      (node (ref "U5") (pin "35_") (pinfunction "VBAT_35_") (pintype "power_in"))
    )
    (net (code "67") (name "VBUS") (class "Default")
      (node (ref "C5") (pin "P$1") (pinfunction "P$1_P$1") (pintype "passive"))
      (node (ref "D1") (pin "C") (pinfunction "C_C") (pintype "passive"))
      (node (ref "D4") (pin "ANODE") (pinfunction "ANODE_ANODE") (pintype "power_in"))
      (node (ref "JP3") (pin "3") (pinfunction "3_3") (pintype "passive"))
      (node (ref "U2") (pin "1") (pinfunction "IN_1") (pintype "power_in"))
      (node (ref "U3") (pin "4") (pinfunction "VDD_4") (pintype "power_in"))
      (node (ref "X3") (pin "1") (pinfunction "5V_1") (pintype "power_in"))
    )
    (net (code "68") (name "VDD_EXT_2V8") (class "Default")
      (node (ref "JP4") (pin "2") (pinfunction "2_2") (pintype "passive"))
      (node (ref "R9") (pin "P$2") (pinfunction "P$2_P$2") (pintype "passive"))
      (node (ref "U5") (pin "40_") (pinfunction "VDD_EXT(2.8VOUT)_40_") (pintype "power_in"))
    )
    (net (code "69") (name "unconnected-(SW1-PadP$3)") (class "Default")
      (node (ref "SW1") (pin "P$3") (pinfunction "P$3_P$3") (pintype "bidirectional"))
    )
    (net (code "70") (name "unconnected-(U2-P4-Pad4)") (class "Default")
      (node (ref "U2") (pin "4") (pinfunction "P4_4") (pintype "bidirectional"))
    )
    (net (code "71") (name "unconnected-(U5-ADC-Pad38_)") (class "Default")
      (node (ref "U5") (pin "38_") (pinfunction "ADC_38_") (pintype "input"))
    )
    (net (code "72") (name "unconnected-(U5-BT_ANT-Pad20_)") (class "Default")
      (node (ref "U5") (pin "20_") (pinfunction "BT_ANT_20_") (pintype "bidirectional"))
    )
    (net (code "73") (name "unconnected-(U5-GPIO1-Pad57_)") (class "Default")
      (node (ref "U5") (pin "57_") (pinfunction "GPIO1_57_") (pintype "bidirectional"))
    )
    (net (code "74") (name "unconnected-(U5-GPIO2-Pad58_)") (class "Default")
      (node (ref "U5") (pin "58_") (pinfunction "GPIO2_58_") (pintype "bidirectional"))
    )
    (net (code "75") (name "unconnected-(U5-MCCA0-Pad49_)") (class "Default")
      (node (ref "U5") (pin "49_") (pinfunction "MCCA0_49_") (pintype "bidirectional"))
    )
    (net (code "76") (name "unconnected-(U5-MCCA1-Pad48_)") (class "Default")
      (node (ref "U5") (pin "48_") (pinfunction "MCCA1_48_") (pintype "bidirectional"))
    )
    (net (code "77") (name "unconnected-(U5-MCCA2-Pad47_)") (class "Default")
      (node (ref "U5") (pin "47_") (pinfunction "MCCA2_47_") (pintype "bidirectional"))
    )
    (net (code "78") (name "unconnected-(U5-MCCA3-Pad46_)") (class "Default")
      (node (ref "U5") (pin "46_") (pinfunction "MCCA3_46_") (pintype "bidirectional"))
    )
    (net (code "79") (name "unconnected-(U5-MCCK-Pad50_)") (class "Default")
      (node (ref "U5") (pin "50_") (pinfunction "MCCK_50_") (pintype "bidirectional"))
    )
    (net (code "80") (name "unconnected-(U5-MCCM0-Pad51_)") (class "Default")
      (node (ref "U5") (pin "51_") (pinfunction "MCCM0_51_") (pintype "bidirectional"))
    )
    (net (code "81") (name "unconnected-(U5-MICN-Pad10_)") (class "Default")
      (node (ref "U5") (pin "10_") (pinfunction "MICN_10_") (pintype "input"))
    )
    (net (code "82") (name "unconnected-(U5-MICP-Pad9_)") (class "Default")
      (node (ref "U5") (pin "9_") (pinfunction "MICP_9_") (pintype "input"))
    )
    (net (code "83") (name "unconnected-(U5-SCL-Pad65_)") (class "Default")
      (node (ref "U5") (pin "65_") (pinfunction "SCL_65_") (pintype "output"))
    )
    (net (code "84") (name "unconnected-(U5-SDA-Pad64_)") (class "Default")
      (node (ref "U5") (pin "64_") (pinfunction "SDA_64_") (pintype "bidirectional"))
    )
    (net (code "85") (name "unconnected-(U5-SIM1_DET-Pad14_)") (class "Default")
      (node (ref "U5") (pin "14_") (pinfunction "SIM1_DET_14_") (pintype "input"))
    )
    (net (code "86") (name "unconnected-(U5-SIM2_CLK-Pad54_)") (class "Default")
      (node (ref "U5") (pin "54_") (pinfunction "SIM2_CLK_54_") (pintype "output"))
    )
    (net (code "87") (name "unconnected-(U5-SIM2_DATA-Pad53_)") (class "Default")
      (node (ref "U5") (pin "53_") (pinfunction "SIM2_DATA_53_") (pintype "bidirectional"))
    )
    (net (code "88") (name "unconnected-(U5-SIM2_DET-Pad52_)") (class "Default")
      (node (ref "U5") (pin "52_") (pinfunction "SIM2_DET_52_") (pintype "input"))
    )
    (net (code "89") (name "unconnected-(U5-SIM2_RST-Pad55_)") (class "Default")
      (node (ref "U5") (pin "55_") (pinfunction "SIM2_RST_55_") (pintype "output"))
    )
    (net (code "90") (name "unconnected-(U5-SPK1N-Pad12_)") (class "Default")
      (node (ref "U5") (pin "12_") (pinfunction "SPK1N_12_") (pintype "output"))
    )
    (net (code "91") (name "unconnected-(U5-SPK1P-Pad11_)") (class "Default")
      (node (ref "U5") (pin "11_") (pinfunction "SPK1P_11_") (pintype "output"))
    )
    (net (code "92") (name "unconnected-(U5-SPK2N-Pad43_)") (class "Default")
      (node (ref "U5") (pin "43_") (pinfunction "SPK2N_43_") (pintype "output"))
    )
    (net (code "93") (name "unconnected-(U5-SPK2P-Pad44_)") (class "Default")
      (node (ref "U5") (pin "44_") (pinfunction "SPK2P_44_") (pintype "output"))
    )
    (net (code "94") (name "unconnected-(U5-UART2_RXD-Pad23_)") (class "Default")
      (node (ref "U5") (pin "23_") (pinfunction "UART2_RXD_23_") (pintype "input"))
    )
    (net (code "95") (name "unconnected-(U5-UART2_TXD-Pad22_)") (class "Default")
      (node (ref "U5") (pin "22_") (pinfunction "UART2_TXD_22_") (pintype "output"))
    )
    (net (code "96") (name "unconnected-(U5-USB_DM-Pad26_)") (class "Default")
      (node (ref "U5") (pin "26_") (pinfunction "USB_DM_26_") (pintype "bidirectional"))
    )
    (net (code "97") (name "unconnected-(U5-USB_DP-Pad25_)") (class "Default")
      (node (ref "U5") (pin "25_") (pinfunction "USB_DP_25_") (pintype "bidirectional"))
    )
    (net (code "98") (name "unconnected-(U7-AUX_CL-Pad7)") (class "Default")
      (node (ref "U7") (pin "7") (pinfunction "AUX_CL_7") (pintype "bidirectional"))
    )
    (net (code "99") (name "unconnected-(U7-AUX_DA-Pad21)") (class "Default")
      (node (ref "U7") (pin "21") (pinfunction "AUX_DA_21") (pintype "bidirectional"))
    )
    (net (code "100") (name "unconnected-(U7-NC1-Pad2)") (class "Default")
      (node (ref "U7") (pin "2") (pinfunction "NC1_2") (pintype "bidirectional"))
    )
    (net (code "101") (name "unconnected-(U7-NC2-Pad3)") (class "Default")
      (node (ref "U7") (pin "3") (pinfunction "NC2_3") (pintype "bidirectional"))
    )
    (net (code "102") (name "unconnected-(U7-NC3-Pad4)") (class "Default")
      (node (ref "U7") (pin "4") (pinfunction "NC3_4") (pintype "bidirectional"))
    )
    (net (code "103") (name "unconnected-(U7-NC4-Pad5)") (class "Default")
      (node (ref "U7") (pin "5") (pinfunction "NC4_5") (pintype "bidirectional"))
    )
    (net (code "104") (name "unconnected-(U7-NC5-Pad6)") (class "Default")
      (node (ref "U7") (pin "6") (pinfunction "NC5_6") (pintype "bidirectional"))
    )
    (net (code "105") (name "unconnected-(U7-NC6-Pad14)") (class "Default")
      (node (ref "U7") (pin "14") (pinfunction "NC6_14") (pintype "bidirectional"))
    )
    (net (code "106") (name "unconnected-(U7-NC7-Pad15)") (class "Default")
      (node (ref "U7") (pin "15") (pinfunction "NC7_15") (pintype "bidirectional"))
    )
    (net (code "107") (name "unconnected-(U7-NC8-Pad16)") (class "Default")
      (node (ref "U7") (pin "16") (pinfunction "NC8_16") (pintype "bidirectional"))
    )
    (net (code "108") (name "unconnected-(U7-NC9-Pad17)") (class "Default")
      (node (ref "U7") (pin "17") (pinfunction "NC9_17") (pintype "bidirectional"))
    )
    (net (code "109") (name "unconnected-(U7-RESV1-Pad19)") (class "Default")
      (node (ref "U7") (pin "19") (pinfunction "RESV1_19") (pintype "bidirectional"))
    )
    (net (code "110") (name "unconnected-(X3-ID-Pad4)") (class "Default")
      (node (ref "X3") (pin "4") (pinfunction "ID_4") (pintype "bidirectional"))
    )
    (net (code "111") (name "unconnected-(X4-SD_DAT1-PadT8)") (class "Default")
      (node (ref "X4") (pin "T8") (pinfunction "SD_DAT1_T8") (pintype "bidirectional"))
    )
    (net (code "112") (name "unconnected-(X4-SD_DAT2-PadT1)") (class "Default")
      (node (ref "X4") (pin "T1") (pinfunction "SD_DAT2_T1") (pintype "bidirectional"))
    )
    (net (code "113") (name "unconnected-(X4-SIM_VPP-PadC6)") (class "Default")
      (node (ref "X4") (pin "C6") (pinfunction "SIM_VPP_C6") (pintype "bidirectional"))
    )
    (net (code "114") (name "~{RESET}") (class "Default")
      (node (ref "JP1") (pin "16") (pinfunction "16_16") (pintype "passive"))
      (node (ref "SW1") (pin "P$1") (pinfunction "P$1_P$1") (pintype "bidirectional"))
      (node (ref "SW1") (pin "P$2") (pinfunction "P$2_P$2") (pintype "bidirectional"))
      (node (ref "U1") (pin "40") (pinfunction "/RESET_40") (pintype "bidirectional"))
    )
  )
)
